# Dash4.net
KiCad netlist of a schematic drawn in EAGLE
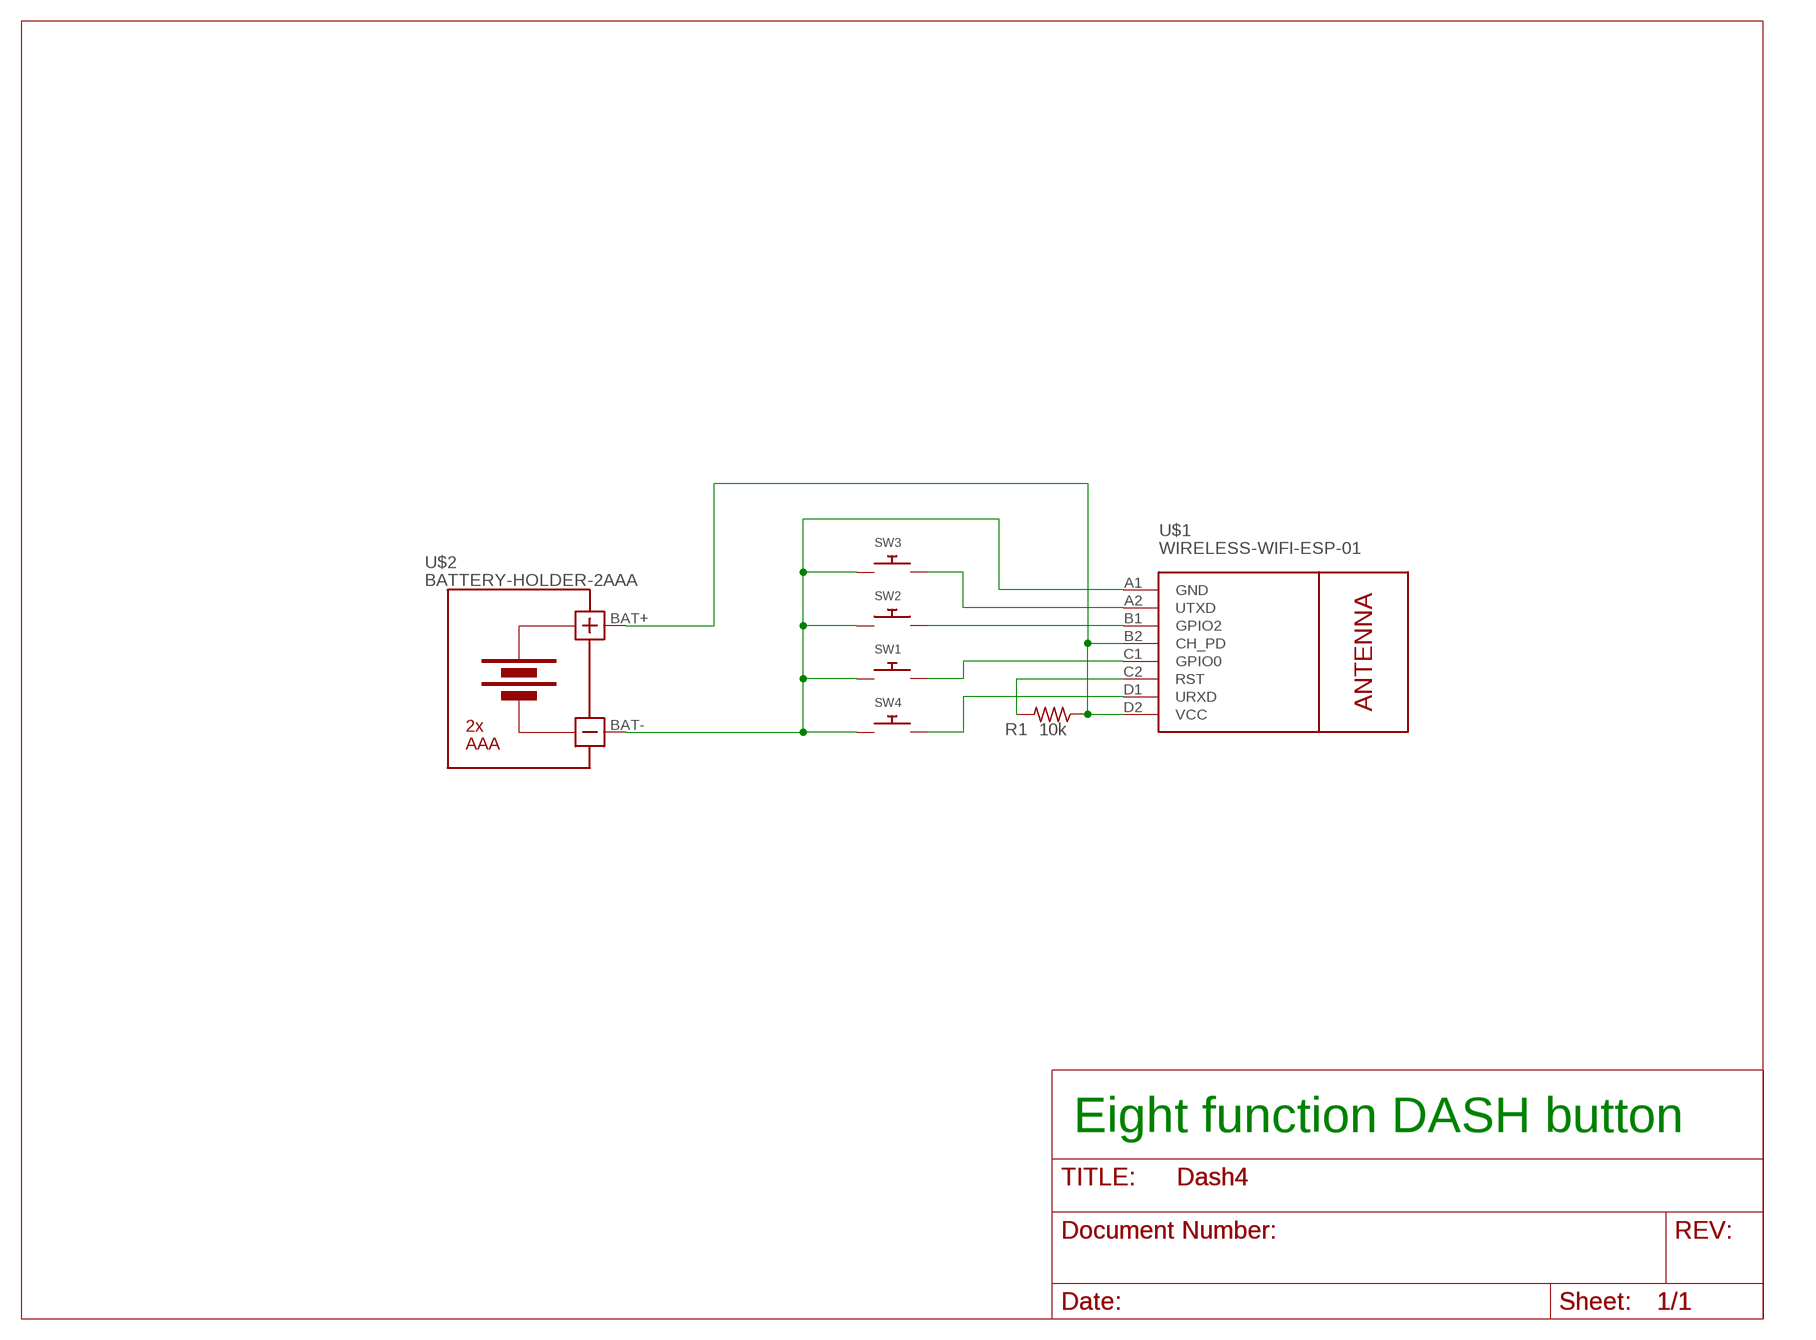
[diagram p0: schematic, sheet 1]

(export (version "E")
  (design (tool "Eeschema 10.0.6"))
  (components
    (comp (ref "R1")
      (value "10k")
      (footprint "eagle-import:0207_9")
      (libsource (lib "eagle-import") (part "R-US_0207/9"))
    )
    (comp (ref "SW1")
      (value "SWITCH_PUSHBUTTONEVQ-PE")
      (footprint "eagle-import:TACT_PANA-EVQ")
      (libsource (lib "eagle-import") (part "SWITCH_PUSHBUTTONEVQ-PE"))
    )
    (comp (ref "SW2")
      (value "SWITCH_PUSHBUTTONEVQ-PE")
      (footprint "eagle-import:TACT_PANA-EVQ")
      (libsource (lib "eagle-import") (part "SWITCH_PUSHBUTTONEVQ-PE"))
    )
    (comp (ref "SW3")
      (value "SWITCH_PUSHBUTTONEVQ-PE")
      (footprint "eagle-import:TACT_PANA-EVQ")
      (libsource (lib "eagle-import") (part "SWITCH_PUSHBUTTONEVQ-PE"))
    )
    (comp (ref "SW4")
      (value "SWITCH_PUSHBUTTONEVQ-PE")
      (footprint "eagle-import:TACT_PANA-EVQ")
      (libsource (lib "eagle-import") (part "SWITCH_PUSHBUTTONEVQ-PE"))
    )
    (comp (ref "U$1")
      (value "WIRELESS-WIFI-ESP-01")
      (footprint "eagle-import:WIRELESS-WIFI-ESP-01")
      (libsource (lib "eagle-import") (part "WIRELESS-WIFI-ESP-01"))
    )
    (comp (ref "U$2")
      (value "BATTERY-HOLDER-2AAA")
      (footprint "eagle-import:BATTERY-HOLDER-2AAA")
      (libsource (lib "eagle-import") (part "BATTERY-HOLDER-2AAA"))
    )
  )
  (nets
    (net (code "1") (name "Net-(U$1-CH_PD)") (class "Default")
      (node (ref "R1") (pin "1") (pinfunction "1_1") (pintype "passive"))
      (node (ref "U$1") (pin "B2") (pinfunction "CH_PD_B2") (pintype "bidirectional"))
      (node (ref "U$1") (pin "D2") (pinfunction "VCC_D2") (pintype "power_in"))
      (node (ref "U$2") (pin "BAT+") (pinfunction "BAT+_BAT+") (pintype "power_in"))
    )
    (net (code "2") (name "Net-(U$1-GND)") (class "Default")
      (node (ref "SW1") (pin "P$1") (pinfunction "P$1_P$1") (pintype "passive"))
      (node (ref "SW2") (pin "P$1") (pinfunction "P$1_P$1") (pintype "passive"))
      (node (ref "SW3") (pin "P$1") (pinfunction "P$1_P$1") (pintype "passive"))
      (node (ref "SW4") (pin "P$1") (pinfunction "P$1_P$1") (pintype "passive"))
      (node (ref "U$1") (pin "A1") (pinfunction "GND_A1") (pintype "power_in"))
      (node (ref "U$2") (pin "BAT-") (pinfunction "BAT-_BAT-") (pintype "power_in"))
    )
    (net (code "3") (name "Net-(U$1-GPIO0)") (class "Default")
      (node (ref "SW1") (pin "P$2") (pinfunction "P$2_P$2") (pintype "passive"))
      (node (ref "U$1") (pin "C1") (pinfunction "GPIO0_C1") (pintype "bidirectional"))
    )
    (net (code "4") (name "Net-(U$1-GPIO2)") (class "Default")
      (node (ref "SW2") (pin "P$2") (pinfunction "P$2_P$2") (pintype "passive"))
      (node (ref "U$1") (pin "B1") (pinfunction "GPIO2_B1") (pintype "bidirectional"))
    )
    (net (code "5") (name "Net-(U$1-RST)") (class "Default")
      (node (ref "R1") (pin "2") (pinfunction "2_2") (pintype "passive"))
      (node (ref "U$1") (pin "C2") (pinfunction "RST_C2") (pintype "bidirectional"))
    )
    (net (code "6") (name "Net-(U$1-URXD)") (class "Default")
      (node (ref "SW4") (pin "P$2") (pinfunction "P$2_P$2") (pintype "passive"))
      (node (ref "U$1") (pin "D1") (pinfunction "URXD_D1") (pintype "bidirectional"))
    )
    (net (code "7") (name "Net-(U$1-UTXD)") (class "Default")
      (node (ref "SW3") (pin "P$2") (pinfunction "P$2_P$2") (pintype "passive"))
      (node (ref "U$1") (pin "A2") (pinfunction "UTXD_A2") (pintype "bidirectional"))
    )
  )
)
